# colororgan.net
KiCad netlist of a schematic drawn in EAGLE
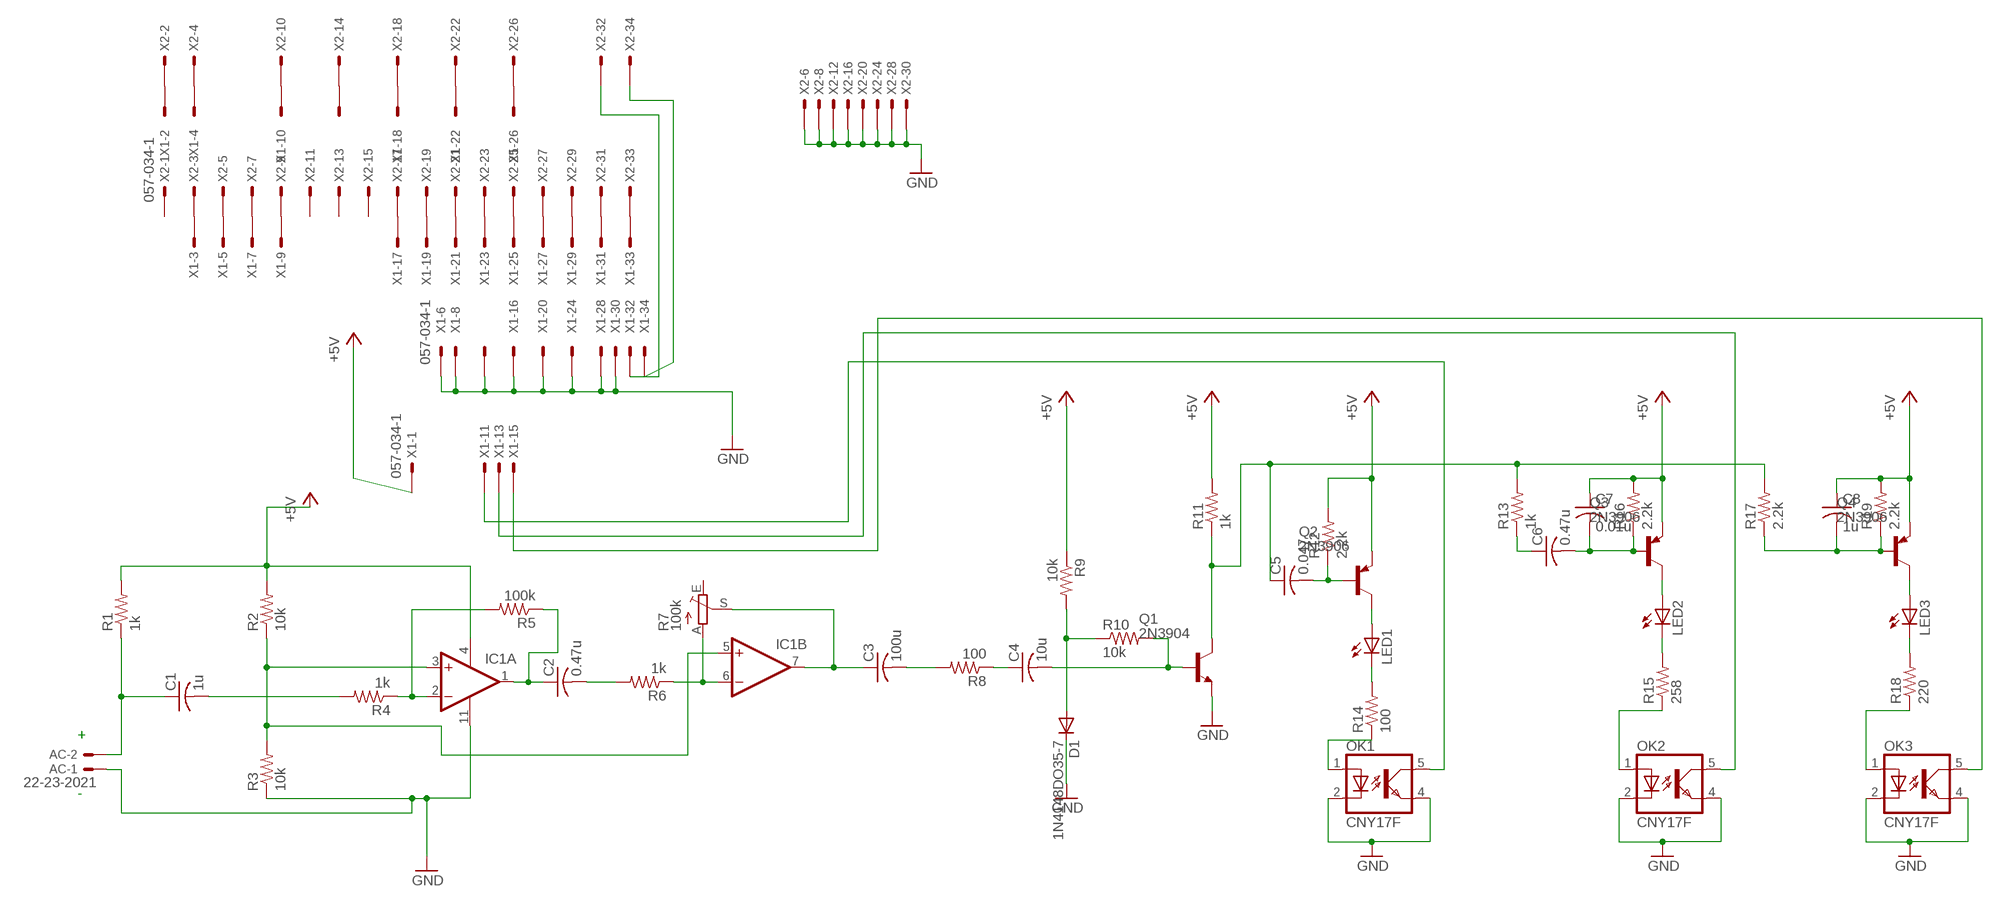
[diagram p0: schematic, sheet 1]

(export (version "E")
  (design (tool "Eeschema 10.0.6"))
  (components
    (comp (ref "AC")
      (value "22-23-2021")
      (footprint "eagle-import:22-23-2021")
      (fields (field (name "MF") "MOLEX"))
      (libsource (lib "eagle-import") (part "22-23-2021"))
    )
    (comp (ref "C1")
      (value "1u")
      (footprint "eagle-import:C025-050X050")
      (libsource (lib "eagle-import") (part "C-US025-050X050"))
    )
    (comp (ref "C2")
      (value "0.47u")
      (footprint "eagle-import:C025-050X050")
      (libsource (lib "eagle-import") (part "C-US025-050X050"))
    )
    (comp (ref "C3")
      (value "100u")
      (footprint "eagle-import:C025-050X050")
      (libsource (lib "eagle-import") (part "C-US025-050X050"))
    )
    (comp (ref "C4")
      (value "10u")
      (footprint "eagle-import:C025-050X050")
      (libsource (lib "eagle-import") (part "C-US025-050X050"))
    )
    (comp (ref "C5")
      (value "0.047")
      (footprint "eagle-import:C025-050X050")
      (libsource (lib "eagle-import") (part "C-US025-050X050"))
    )
    (comp (ref "C6")
      (value "0.47u")
      (footprint "eagle-import:C025-050X050")
      (libsource (lib "eagle-import") (part "C-US025-050X050"))
    )
    (comp (ref "C7")
      (value "0.01u")
      (footprint "eagle-import:C025-050X050")
      (libsource (lib "eagle-import") (part "C-US025-050X050"))
    )
    (comp (ref "C8")
      (value "1u")
      (footprint "eagle-import:C025-050X050")
      (libsource (lib "eagle-import") (part "C-US025-050X050"))
    )
    (comp (ref "D1")
      (value "1N4148DO35-7")
      (footprint "eagle-import:DO35-7")
      (libsource (lib "eagle-import") (part "1N4148DO35-7"))
    )
    (comp (ref "IC1")
      (value "LMV324THR")
      (footprint "eagle-import:DIL14")
      (libsource (lib "eagle-import") (part "LMV324?THR"))
    )
    (comp (ref "LED1")
      (value "LED3MM")
      (footprint "eagle-import:LED3MM")
      (libsource (lib "eagle-import") (part "LED3MM"))
    )
    (comp (ref "LED2")
      (value "LED3MM")
      (footprint "eagle-import:LED3MM")
      (libsource (lib "eagle-import") (part "LED3MM"))
    )
    (comp (ref "LED3")
      (value "LED3MM")
      (footprint "eagle-import:LED3MM")
      (libsource (lib "eagle-import") (part "LED3MM"))
    )
    (comp (ref "OK1")
      (value "CNY17F")
      (footprint "eagle-import:DIL06")
      (fields (field (name "MF") "VISHAY/TELEFUNKEN") (field (name "MPN") "CNY17F-3"))
      (libsource (lib "eagle-import") (part "CNY17F"))
    )
    (comp (ref "OK2")
      (value "CNY17F")
      (footprint "eagle-import:DIL06")
      (fields (field (name "MF") "VISHAY/TELEFUNKEN") (field (name "MPN") "CNY17F-3"))
      (libsource (lib "eagle-import") (part "CNY17F"))
    )
    (comp (ref "OK3")
      (value "CNY17F")
      (footprint "eagle-import:DIL06")
      (fields (field (name "MF") "VISHAY/TELEFUNKEN") (field (name "MPN") "CNY17F-3"))
      (libsource (lib "eagle-import") (part "CNY17F"))
    )
    (comp (ref "Q1")
      (value "2N3904")
      (footprint "eagle-import:TO92")
      (libsource (lib "eagle-import") (part "2N3904"))
    )
    (comp (ref "Q2")
      (value "2N3906")
      (footprint "eagle-import:TO92")
      (libsource (lib "eagle-import") (part "2N3906"))
    )
    (comp (ref "Q3")
      (value "2N3906")
      (footprint "eagle-import:TO92")
      (libsource (lib "eagle-import") (part "2N3906"))
    )
    (comp (ref "Q4")
      (value "2N3906")
      (footprint "eagle-import:TO92")
      (libsource (lib "eagle-import") (part "2N3906"))
    )
    (comp (ref "R1")
      (value "1k")
      (footprint "eagle-import:0207_10")
      (libsource (lib "eagle-import") (part "R-US_0207/10"))
    )
    (comp (ref "R2")
      (value "10k")
      (footprint "eagle-import:0207_10")
      (libsource (lib "eagle-import") (part "R-US_0207/10"))
    )
    (comp (ref "R3")
      (value "10k")
      (footprint "eagle-import:0207_10")
      (libsource (lib "eagle-import") (part "R-US_0207/10"))
    )
    (comp (ref "R4")
      (value "1k")
      (footprint "eagle-import:0207_10")
      (libsource (lib "eagle-import") (part "R-US_0207/10"))
    )
    (comp (ref "R5")
      (value "100k")
      (footprint "eagle-import:0207_10")
      (libsource (lib "eagle-import") (part "R-US_0207/10"))
    )
    (comp (ref "R6")
      (value "1k")
      (footprint "eagle-import:0207_10")
      (libsource (lib "eagle-import") (part "R-US_0207/10"))
    )
    (comp (ref "R7")
      (value "100k")
      (footprint "eagle-import:RS3")
      (libsource (lib "eagle-import") (part "TRIM_EU-RS3"))
    )
    (comp (ref "R8")
      (value "100")
      (footprint "eagle-import:0207_10")
      (libsource (lib "eagle-import") (part "R-US_0207/10"))
    )
    (comp (ref "R9")
      (value "10k")
      (footprint "eagle-import:0207_10")
      (libsource (lib "eagle-import") (part "R-US_0207/10"))
    )
    (comp (ref "R10")
      (value "10k")
      (footprint "eagle-import:0207_10")
      (libsource (lib "eagle-import") (part "R-US_0207/10"))
    )
    (comp (ref "R11")
      (value "1k")
      (footprint "eagle-import:0207_10")
      (libsource (lib "eagle-import") (part "R-US_0207/10"))
    )
    (comp (ref "R12")
      (value "2.2k")
      (footprint "eagle-import:0207_10")
      (libsource (lib "eagle-import") (part "R-US_0207/10"))
    )
    (comp (ref "R13")
      (value "1k")
      (footprint "eagle-import:0207_10")
      (libsource (lib "eagle-import") (part "R-US_0207/10"))
    )
    (comp (ref "R14")
      (value "100")
      (footprint "eagle-import:0207_10")
      (libsource (lib "eagle-import") (part "R-US_0207/10"))
    )
    (comp (ref "R15")
      (value "258")
      (footprint "eagle-import:0207_10")
      (libsource (lib "eagle-import") (part "R-US_0207/10"))
    )
    (comp (ref "R16")
      (value "2.2k")
      (footprint "eagle-import:0207_10")
      (libsource (lib "eagle-import") (part "R-US_0207/10"))
    )
    (comp (ref "R17")
      (value "2.2k")
      (footprint "eagle-import:0207_10")
      (libsource (lib "eagle-import") (part "R-US_0207/10"))
    )
    (comp (ref "R18")
      (value "220")
      (footprint "eagle-import:0207_10")
      (libsource (lib "eagle-import") (part "R-US_0207/10"))
    )
    (comp (ref "R19")
      (value "2.2k")
      (footprint "eagle-import:0207_10")
      (libsource (lib "eagle-import") (part "R-US_0207/10"))
    )
    (comp (ref "X1")
      (value "057-034-1")
      (footprint "eagle-import:057-034-1")
      (libsource (lib "eagle-import") (part "057-034-1"))
    )
    (comp (ref "X2")
      (value "057-034-1")
      (footprint "eagle-import:057-034-1")
      (libsource (lib "eagle-import") (part "057-034-1"))
    )
  )
  (nets
    (net (code "1") (name "+5V") (class "Default")
      (node (ref "C7") (pin "1") (pinfunction "1_1") (pintype "passive"))
      (node (ref "C8") (pin "1") (pinfunction "1_1") (pintype "passive"))
      (node (ref "IC1") (pin "4") (pinfunction "V+_4") (pintype "power_in"))
      (node (ref "Q2") (pin "3") (pinfunction "E_3") (pintype "passive"))
      (node (ref "Q3") (pin "3") (pinfunction "E_3") (pintype "passive"))
      (node (ref "Q4") (pin "3") (pinfunction "E_3") (pintype "passive"))
      (node (ref "R1") (pin "2") (pinfunction "2_2") (pintype "passive"))
      (node (ref "R11") (pin "2") (pinfunction "2_2") (pintype "passive"))
      (node (ref "R12") (pin "2") (pinfunction "2_2") (pintype "passive"))
      (node (ref "R16") (pin "2") (pinfunction "2_2") (pintype "passive"))
      (node (ref "R19") (pin "2") (pinfunction "2_2") (pintype "passive"))
      (node (ref "R2") (pin "2") (pinfunction "2_2") (pintype "passive"))
      (node (ref "R9") (pin "1") (pinfunction "1_1") (pintype "passive"))
      (node (ref "X1") (pin "1") (pinfunction "S_1") (pintype "passive"))
    )
    (net (code "2") (name "GND") (class "Default")
      (node (ref "AC") (pin "1") (pinfunction "S_1") (pintype "passive"))
      (node (ref "D1") (pin "C") (pinfunction "C_C") (pintype "passive"))
      (node (ref "IC1") (pin "11") (pinfunction "V-_11") (pintype "power_in"))
      (node (ref "OK1") (pin "2") (pinfunction "C_2") (pintype "passive"))
      (node (ref "OK1") (pin "4") (pinfunction "EMIT_4") (pintype "passive"))
      (node (ref "OK2") (pin "2") (pinfunction "C_2") (pintype "passive"))
      (node (ref "OK2") (pin "4") (pinfunction "EMIT_4") (pintype "passive"))
      (node (ref "OK3") (pin "2") (pinfunction "C_2") (pintype "passive"))
      (node (ref "OK3") (pin "4") (pinfunction "EMIT_4") (pintype "passive"))
      (node (ref "Q1") (pin "3") (pinfunction "E_3") (pintype "passive"))
      (node (ref "R3") (pin "1") (pinfunction "1_1") (pintype "passive"))
      (node (ref "X1") (pin "12") (pinfunction "S_12") (pintype "passive"))
      (node (ref "X1") (pin "16") (pinfunction "S_16") (pintype "passive"))
      (node (ref "X1") (pin "20") (pinfunction "S_20") (pintype "passive"))
      (node (ref "X1") (pin "24") (pinfunction "S_24") (pintype "passive"))
      (node (ref "X1") (pin "28") (pinfunction "S_28") (pintype "passive"))
      (node (ref "X1") (pin "30") (pinfunction "S_30") (pintype "passive"))
      (node (ref "X1") (pin "6") (pinfunction "S_6") (pintype "passive"))
      (node (ref "X1") (pin "8") (pinfunction "S_8") (pintype "passive"))
      (node (ref "X2") (pin "12") (pinfunction "S_12") (pintype "passive"))
      (node (ref "X2") (pin "16") (pinfunction "S_16") (pintype "passive"))
      (node (ref "X2") (pin "20") (pinfunction "S_20") (pintype "passive"))
      (node (ref "X2") (pin "24") (pinfunction "S_24") (pintype "passive"))
      (node (ref "X2") (pin "28") (pinfunction "S_28") (pintype "passive"))
      (node (ref "X2") (pin "30") (pinfunction "S_30") (pintype "passive"))
      (node (ref "X2") (pin "6") (pinfunction "S_6") (pintype "passive"))
      (node (ref "X2") (pin "8") (pinfunction "S_8") (pintype "passive"))
    )
    (net (code "3") (name "Net-(ACB-S)") (class "Default")
      (node (ref "AC") (pin "2") (pinfunction "S_2") (pintype "passive"))
      (node (ref "C1") (pin "1") (pinfunction "1_1") (pintype "passive"))
      (node (ref "R1") (pin "1") (pinfunction "1_1") (pintype "passive"))
    )
    (net (code "4") (name "Net-(C1-Pad2)") (class "Default")
      (node (ref "C1") (pin "2") (pinfunction "2_2") (pintype "passive"))
      (node (ref "R4") (pin "2") (pinfunction "2_2") (pintype "passive"))
    )
    (net (code "5") (name "Net-(C2-Pad2)") (class "Default")
      (node (ref "C2") (pin "2") (pinfunction "2_2") (pintype "passive"))
      (node (ref "R6") (pin "2") (pinfunction "2_2") (pintype "passive"))
    )
    (net (code "6") (name "Net-(C3-Pad2)") (class "Default")
      (node (ref "C3") (pin "2") (pinfunction "2_2") (pintype "passive"))
      (node (ref "R8") (pin "2") (pinfunction "2_2") (pintype "passive"))
    )
    (net (code "7") (name "Net-(C4-Pad1)") (class "Default")
      (node (ref "C4") (pin "1") (pinfunction "1_1") (pintype "passive"))
      (node (ref "R8") (pin "1") (pinfunction "1_1") (pintype "passive"))
    )
    (net (code "8") (name "Net-(C6-Pad1)") (class "Default")
      (node (ref "C6") (pin "1") (pinfunction "1_1") (pintype "passive"))
      (node (ref "R13") (pin "1") (pinfunction "1_1") (pintype "passive"))
    )
    (net (code "9") (name "Net-(D1-PadA)") (class "Default")
      (node (ref "D1") (pin "A") (pinfunction "A_A") (pintype "passive"))
      (node (ref "R10") (pin "1") (pinfunction "1_1") (pintype "passive"))
      (node (ref "R9") (pin "2") (pinfunction "2_2") (pintype "passive"))
    )
    (net (code "10") (name "Net-(IC1A-+IN)") (class "Default")
      (node (ref "IC1") (pin "3") (pinfunction "+IN_3") (pintype "input"))
      (node (ref "IC1") (pin "5") (pinfunction "+IN_5") (pintype "input"))
      (node (ref "R2") (pin "1") (pinfunction "1_1") (pintype "passive"))
      (node (ref "R3") (pin "2") (pinfunction "2_2") (pintype "passive"))
    )
    (net (code "11") (name "Net-(IC1A--IN)") (class "Default")
      (node (ref "IC1") (pin "2") (pinfunction "-IN_2") (pintype "input"))
      (node (ref "R4") (pin "1") (pinfunction "1_1") (pintype "passive"))
      (node (ref "R5") (pin "2") (pinfunction "2_2") (pintype "passive"))
    )
    (net (code "12") (name "Net-(IC1A-OUT)") (class "Default")
      (node (ref "C2") (pin "1") (pinfunction "1_1") (pintype "passive"))
      (node (ref "IC1") (pin "1") (pinfunction "OUT_1") (pintype "output"))
      (node (ref "R5") (pin "1") (pinfunction "1_1") (pintype "passive"))
    )
    (net (code "13") (name "Net-(IC1B--IN)") (class "Default")
      (node (ref "IC1") (pin "6") (pinfunction "-IN_6") (pintype "input"))
      (node (ref "R6") (pin "1") (pinfunction "1_1") (pintype "passive"))
      (node (ref "R7") (pin "A") (pinfunction "A_A") (pintype "passive"))
    )
    (net (code "14") (name "Net-(IC1B-OUT)") (class "Default")
      (node (ref "C3") (pin "1") (pinfunction "1_1") (pintype "passive"))
      (node (ref "IC1") (pin "7") (pinfunction "OUT_7") (pintype "output"))
      (node (ref "R7") (pin "S") (pinfunction "S_S") (pintype "passive"))
    )
    (net (code "15") (name "Net-(LED1-C)") (class "Default")
      (node (ref "LED1") (pin "K") (pinfunction "C_K") (pintype "passive"))
      (node (ref "R14") (pin "2") (pinfunction "2_2") (pintype "passive"))
    )
    (net (code "16") (name "Net-(LED2-C)") (class "Default")
      (node (ref "LED2") (pin "K") (pinfunction "C_K") (pintype "passive"))
      (node (ref "R15") (pin "2") (pinfunction "2_2") (pintype "passive"))
    )
    (net (code "17") (name "Net-(LED3-C)") (class "Default")
      (node (ref "LED3") (pin "K") (pinfunction "C_K") (pintype "passive"))
      (node (ref "R18") (pin "2") (pinfunction "2_2") (pintype "passive"))
    )
    (net (code "18") (name "Net-(OK1-A)") (class "Default")
      (node (ref "OK1") (pin "1") (pinfunction "A_1") (pintype "passive"))
      (node (ref "R14") (pin "1") (pinfunction "1_1") (pintype "passive"))
    )
    (net (code "19") (name "Net-(OK1-COL)") (class "Default")
      (node (ref "OK1") (pin "5") (pinfunction "COL_5") (pintype "passive"))
      (node (ref "X1") (pin "11") (pinfunction "S_11") (pintype "passive"))
    )
    (net (code "20") (name "Net-(OK2-A)") (class "Default")
      (node (ref "OK2") (pin "1") (pinfunction "A_1") (pintype "passive"))
      (node (ref "R15") (pin "1") (pinfunction "1_1") (pintype "passive"))
    )
    (net (code "21") (name "Net-(OK2-COL)") (class "Default")
      (node (ref "OK2") (pin "5") (pinfunction "COL_5") (pintype "passive"))
      (node (ref "X1") (pin "13") (pinfunction "S_13") (pintype "passive"))
    )
    (net (code "22") (name "Net-(OK3-A)") (class "Default")
      (node (ref "OK3") (pin "1") (pinfunction "A_1") (pintype "passive"))
      (node (ref "R18") (pin "1") (pinfunction "1_1") (pintype "passive"))
    )
    (net (code "23") (name "Net-(OK3-COL)") (class "Default")
      (node (ref "OK3") (pin "5") (pinfunction "COL_5") (pintype "passive"))
      (node (ref "X1") (pin "15") (pinfunction "S_15") (pintype "passive"))
    )
    (net (code "24") (name "Net-(Q1-B)") (class "Default")
      (node (ref "C4") (pin "2") (pinfunction "2_2") (pintype "passive"))
      (node (ref "Q1") (pin "2") (pinfunction "B_2") (pintype "passive"))
      (node (ref "R10") (pin "2") (pinfunction "2_2") (pintype "passive"))
    )
    (net (code "25") (name "Net-(Q1-C)") (class "Default")
      (node (ref "C5") (pin "1") (pinfunction "1_1") (pintype "passive"))
      (node (ref "Q1") (pin "1") (pinfunction "C_1") (pintype "passive"))
      (node (ref "R11") (pin "1") (pinfunction "1_1") (pintype "passive"))
      (node (ref "R13") (pin "2") (pinfunction "2_2") (pintype "passive"))
      (node (ref "R17") (pin "2") (pinfunction "2_2") (pintype "passive"))
    )
    (net (code "26") (name "Net-(Q2-B)") (class "Default")
      (node (ref "C5") (pin "2") (pinfunction "2_2") (pintype "passive"))
      (node (ref "Q2") (pin "2") (pinfunction "B_2") (pintype "passive"))
      (node (ref "R12") (pin "1") (pinfunction "1_1") (pintype "passive"))
    )
    (net (code "27") (name "Net-(Q2-C)") (class "Default")
      (node (ref "LED1") (pin "A") (pinfunction "A_A") (pintype "passive"))
      (node (ref "Q2") (pin "1") (pinfunction "C_1") (pintype "passive"))
    )
    (net (code "28") (name "Net-(Q3-B)") (class "Default")
      (node (ref "C6") (pin "2") (pinfunction "2_2") (pintype "passive"))
      (node (ref "C7") (pin "2") (pinfunction "2_2") (pintype "passive"))
      (node (ref "Q3") (pin "2") (pinfunction "B_2") (pintype "passive"))
      (node (ref "R16") (pin "1") (pinfunction "1_1") (pintype "passive"))
    )
    (net (code "29") (name "Net-(Q3-C)") (class "Default")
      (node (ref "LED2") (pin "A") (pinfunction "A_A") (pintype "passive"))
      (node (ref "Q3") (pin "1") (pinfunction "C_1") (pintype "passive"))
    )
    (net (code "30") (name "Net-(Q4-B)") (class "Default")
      (node (ref "C8") (pin "2") (pinfunction "2_2") (pintype "passive"))
      (node (ref "Q4") (pin "2") (pinfunction "B_2") (pintype "passive"))
      (node (ref "R17") (pin "1") (pinfunction "1_1") (pintype "passive"))
      (node (ref "R19") (pin "1") (pinfunction "1_1") (pintype "passive"))
    )
    (net (code "31") (name "Net-(Q4-C)") (class "Default")
      (node (ref "LED3") (pin "A") (pinfunction "A_A") (pintype "passive"))
      (node (ref "Q4") (pin "1") (pinfunction "C_1") (pintype "passive"))
    )
    (net (code "32") (name "Net-(X1AA-S)") (class "Default")
      (node (ref "X1") (pin "33") (pinfunction "S_33") (pintype "passive"))
      (node (ref "X2") (pin "33") (pinfunction "S_33") (pintype "passive"))
    )
    (net (code "33") (name "Net-(X1AB-S)") (class "Default")
      (node (ref "X1") (pin "34") (pinfunction "S_34") (pintype "passive"))
      (node (ref "X2") (pin "34") (pinfunction "S_34") (pintype "passive"))
    )
    (net (code "34") (name "Net-(X1AC-S)") (class "Default")
      (node (ref "X1") (pin "4") (pinfunction "S_4") (pintype "passive"))
      (node (ref "X2") (pin "4") (pinfunction "S_4") (pintype "passive"))
    )
    (net (code "35") (name "Net-(X1AD-S)") (class "Default")
      (node (ref "X1") (pin "5") (pinfunction "S_5") (pintype "passive"))
      (node (ref "X2") (pin "5") (pinfunction "S_5") (pintype "passive"))
    )
    (net (code "36") (name "Net-(X1AF-S)") (class "Default")
      (node (ref "X1") (pin "7") (pinfunction "S_7") (pintype "passive"))
      (node (ref "X2") (pin "7") (pinfunction "S_7") (pintype "passive"))
    )
    (net (code "37") (name "Net-(X1AH-S)") (class "Default")
      (node (ref "X1") (pin "9") (pinfunction "S_9") (pintype "passive"))
      (node (ref "X2") (pin "9") (pinfunction "S_9") (pintype "passive"))
    )
    (net (code "38") (name "Net-(X1B-S)") (class "Default")
      (node (ref "X1") (pin "10") (pinfunction "S_10") (pintype "passive"))
      (node (ref "X2") (pin "10") (pinfunction "S_10") (pintype "passive"))
    )
    (net (code "39") (name "Net-(X1F-S)") (class "Default")
      (node (ref "X1") (pin "14") (pinfunction "S_14") (pintype "passive"))
      (node (ref "X2") (pin "14") (pinfunction "S_14") (pintype "passive"))
    )
    (net (code "40") (name "Net-(X1I-S)") (class "Default")
      (node (ref "X1") (pin "17") (pinfunction "S_17") (pintype "passive"))
      (node (ref "X2") (pin "17") (pinfunction "S_17") (pintype "passive"))
    )
    (net (code "41") (name "Net-(X1J-S)") (class "Default")
      (node (ref "X1") (pin "18") (pinfunction "S_18") (pintype "passive"))
      (node (ref "X2") (pin "18") (pinfunction "S_18") (pintype "passive"))
    )
    (net (code "42") (name "Net-(X1K-S)") (class "Default")
      (node (ref "X1") (pin "19") (pinfunction "S_19") (pintype "passive"))
      (node (ref "X2") (pin "19") (pinfunction "S_19") (pintype "passive"))
    )
    (net (code "43") (name "Net-(X1L-S)") (class "Default")
      (node (ref "X1") (pin "2") (pinfunction "S_2") (pintype "passive"))
      (node (ref "X2") (pin "2") (pinfunction "S_2") (pintype "passive"))
    )
    (net (code "44") (name "Net-(X1N-S)") (class "Default")
      (node (ref "X1") (pin "21") (pinfunction "S_21") (pintype "passive"))
      (node (ref "X2") (pin "21") (pinfunction "S_21") (pintype "passive"))
    )
    (net (code "45") (name "Net-(X1O-S)") (class "Default")
      (node (ref "X1") (pin "22") (pinfunction "S_22") (pintype "passive"))
      (node (ref "X2") (pin "22") (pinfunction "S_22") (pintype "passive"))
    )
    (net (code "46") (name "Net-(X1P-S)") (class "Default")
      (node (ref "X1") (pin "23") (pinfunction "S_23") (pintype "passive"))
      (node (ref "X2") (pin "23") (pinfunction "S_23") (pintype "passive"))
    )
    (net (code "47") (name "Net-(X1R-S)") (class "Default")
      (node (ref "X1") (pin "25") (pinfunction "S_25") (pintype "passive"))
      (node (ref "X2") (pin "25") (pinfunction "S_25") (pintype "passive"))
    )
    (net (code "48") (name "Net-(X1S-S)") (class "Default")
      (node (ref "X1") (pin "26") (pinfunction "S_26") (pintype "passive"))
      (node (ref "X2") (pin "26") (pinfunction "S_26") (pintype "passive"))
    )
    (net (code "49") (name "Net-(X1T-S)") (class "Default")
      (node (ref "X1") (pin "27") (pinfunction "S_27") (pintype "passive"))
      (node (ref "X2") (pin "27") (pinfunction "S_27") (pintype "passive"))
    )
    (net (code "50") (name "Net-(X1V-S)") (class "Default")
      (node (ref "X1") (pin "29") (pinfunction "S_29") (pintype "passive"))
      (node (ref "X2") (pin "29") (pinfunction "S_29") (pintype "passive"))
    )
    (net (code "51") (name "Net-(X1W-S)") (class "Default")
      (node (ref "X1") (pin "3") (pinfunction "S_3") (pintype "passive"))
      (node (ref "X2") (pin "3") (pinfunction "S_3") (pintype "passive"))
    )
    (net (code "52") (name "Net-(X1Y-S)") (class "Default")
      (node (ref "X1") (pin "31") (pinfunction "S_31") (pintype "passive"))
      (node (ref "X2") (pin "31") (pinfunction "S_31") (pintype "passive"))
    )
    (net (code "53") (name "Net-(X1Z-S)") (class "Default")
      (node (ref "X1") (pin "32") (pinfunction "S_32") (pintype "passive"))
      (node (ref "X2") (pin "32") (pinfunction "S_32") (pintype "passive"))
    )
    (net (code "54") (name "unconnected-(R7-PadE)") (class "Default")
      (node (ref "R7") (pin "E") (pinfunction "E_E") (pintype "passive"))
    )
    (net (code "55") (name "unconnected-(X2A-S-Pad1)") (class "Default")
      (node (ref "X2") (pin "1") (pinfunction "S_1") (pintype "passive"))
    )
    (net (code "56") (name "unconnected-(X2C-S-Pad11)") (class "Default")
      (node (ref "X2") (pin "11") (pinfunction "S_11") (pintype "passive"))
    )
    (net (code "57") (name "unconnected-(X2E-S-Pad13)") (class "Default")
      (node (ref "X2") (pin "13") (pinfunction "S_13") (pintype "passive"))
    )
    (net (code "58") (name "unconnected-(X2G-S-Pad15)") (class "Default")
      (node (ref "X2") (pin "15") (pinfunction "S_15") (pintype "passive"))
    )
  )
)
